# 2_MODUE.net
KiCad netlist of a schematic drawn in Altium Designer
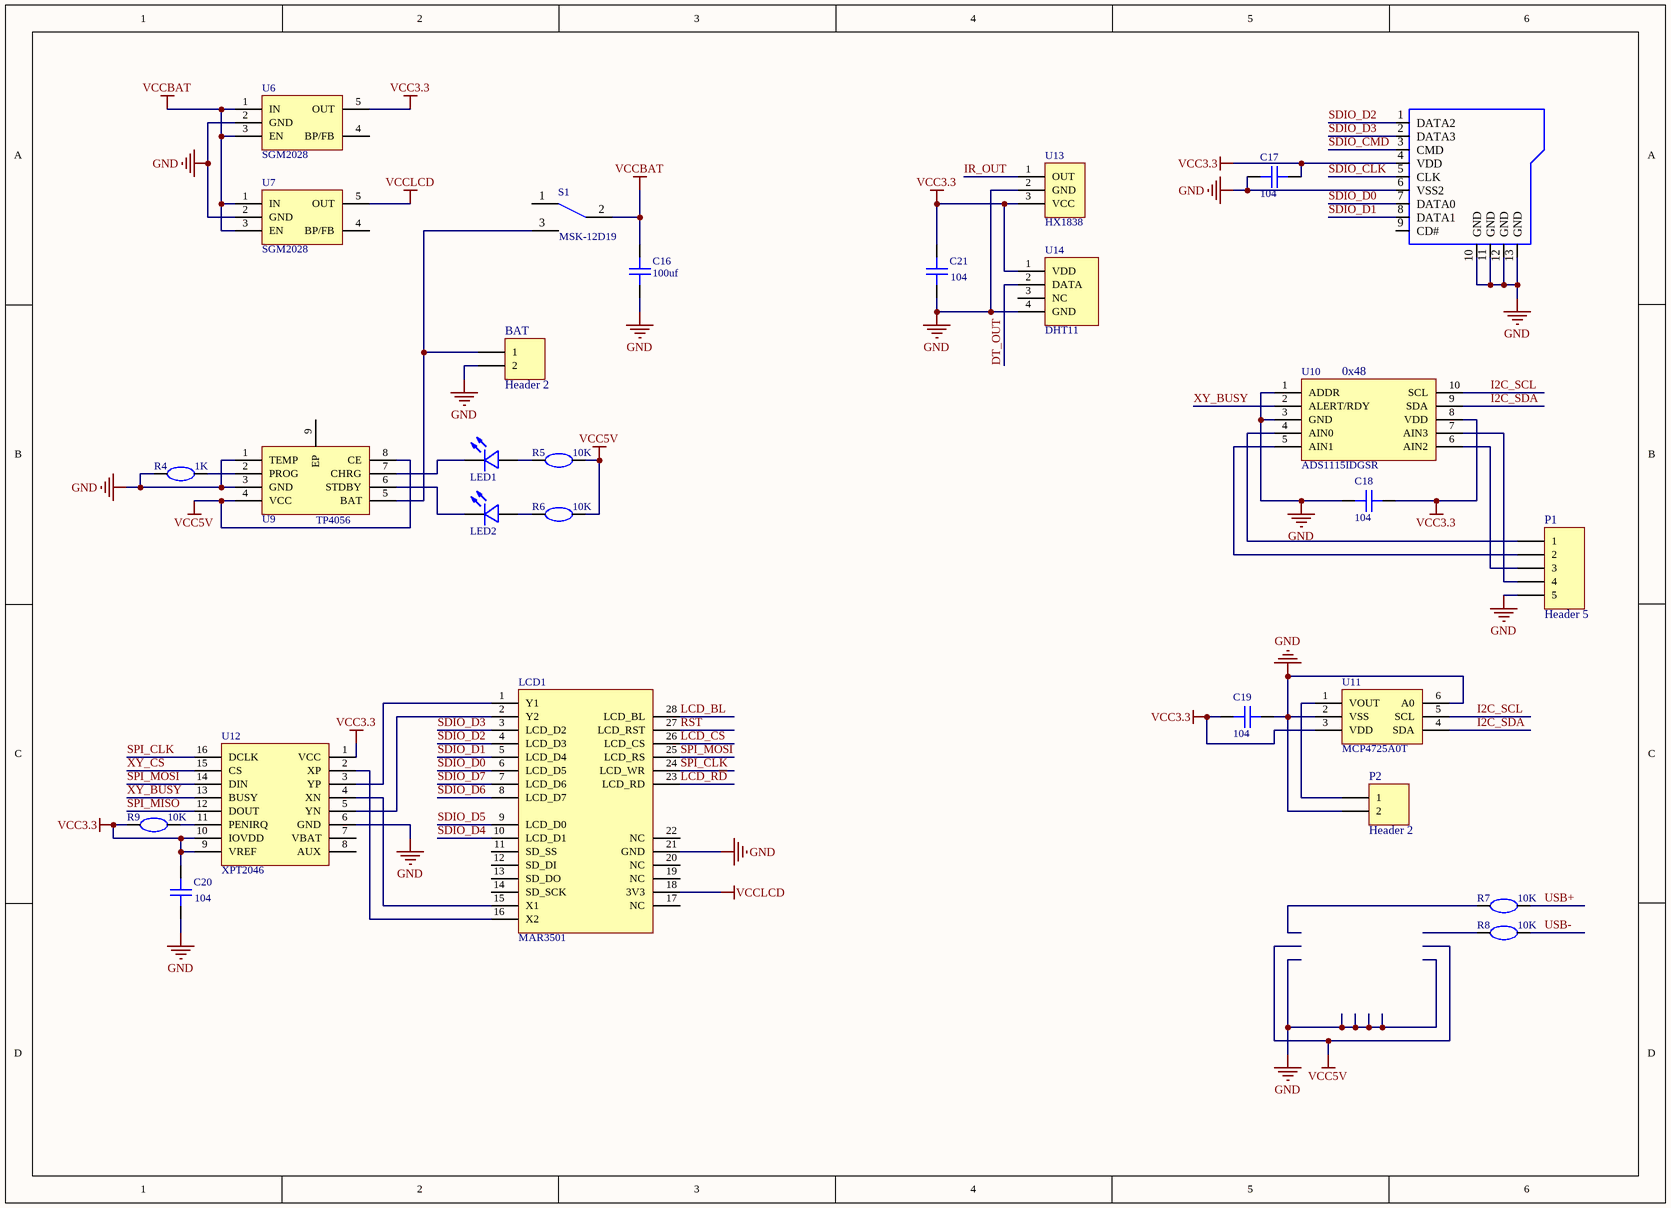
[diagram p0: 2_MODUE.schdoc]

(export (version "E")
  (design (tool "Eeschema 10.0.6"))
  (components
    (comp (ref "BAT")
      (value "Header 2")
      (footprint "HDR1X2")
      (description "Header, 2-Pin")
      (fields (field (name "PUBLISHER") "Altium Limited"))
      (libsource (lib "Miscellaneous Connectors") (part "Header 2"))
    )
    (comp (ref "C16") (value "100uf") (footprint "3528") (libsource (lib "sch") (part "CAP")))
    (comp (ref "C17") (value "104") (footprint "0402R") (libsource (lib "sch") (part "CAP")))
    (comp (ref "C18") (value "104") (footprint "0402R") (libsource (lib "sch") (part "CAP")))
    (comp (ref "C19") (value "104") (footprint "0402R") (libsource (lib "sch") (part "CAP")))
    (comp (ref "C20") (value "104") (footprint "0402R") (libsource (lib "sch") (part "CAP")))
    (comp (ref "C21") (value "104") (footprint "0402R") (libsource (lib "sch") (part "CAP")))
    (comp (ref "LCD1") (value "MAR3501") (footprint "MAR3501") (libsource (lib "sch") (part "MAR3501")))
    (comp (ref "LED1") (value "L-C292WDT-5A-YY") (footprint "0805") (libsource (lib "sch") (part "LED")))
    (comp (ref "LED2") (value "L-C292WDT-5A-YY") (footprint "0805") (libsource (lib "sch") (part "LED")))
    (comp (ref "P1")
      (value "Header 5")
      (footprint "HDR1X5")
      (description "Header, 5-Pin")
      (fields (field (name "PUBLISHER") "Altium Limited"))
      (libsource (lib "Miscellaneous Connectors") (part "Header 5"))
    )
    (comp (ref "P2")
      (value "Header 2")
      (footprint "HDR1X2")
      (description "Header, 2-Pin")
      (fields (field (name "PUBLISHER") "Altium Limited"))
      (libsource (lib "Miscellaneous Connectors") (part "Header 2"))
    )
    (comp (ref "R4") (value "1K") (footprint "0402R") (libsource (lib "sch") (part "RST")))
    (comp (ref "R5") (value "10K") (footprint "0402R") (libsource (lib "sch") (part "RST")))
    (comp (ref "R6") (value "10K") (footprint "0402R") (libsource (lib "sch") (part "RST")))
    (comp (ref "R7") (value "10K") (footprint "0805") (libsource (lib "sch") (part "RST")))
    (comp (ref "R8") (value "10K") (footprint "0805") (libsource (lib "sch") (part "RST")))
    (comp (ref "R9") (value "10K") (footprint "0402R") (libsource (lib "sch") (part "RST")))
    (comp (ref "S1")
      (value "MSK-12D19")
      (footprint "MSK-12D19")
      (fields (field (name "NAME") "MSK-12D19"))
      (libsource (lib "sch") (part "MSK-12D19"))
    )
    (comp (ref "TF1") (value "TF") (footprint "TF-SMD_XKTF-N02-N_1") (libsource (lib "sch") (part "TF")))
    (comp (ref "U6")
      (value "SGM2028")
      (footprint "SOT-23-5_L3.0-W1.7-P0.95-LS2.8-BR")
      (libsource (lib "sch") (part "SGM2028"))
    )
    (comp (ref "U7")
      (value "SGM2028")
      (footprint "SOT-23-5_L3.0-W1.7-P0.95-LS2.8-BR")
      (libsource (lib "sch") (part "SGM2028"))
    )
    (comp (ref "U9")
      (value "TP4056")
      (footprint "ESOP-8_L4.9-W3.9-P1.27-LS6.0-BL-EP")
      (libsource (lib "sch") (part "TP4056"))
    )
    (comp (ref "U10")
      (value "ADS1115IDGSR")
      (footprint "MSOP-10_L3.0-W3.0-P0.50-LS5.0-BL")
      (libsource (lib "sch") (part "ADS1115IDGSR"))
    )
    (comp (ref "U11")
      (value "MCP4725A0T")
      (footprint "SOT-23-6_L2.9-W1.6-P0.95-LS2.8-BR")
      (libsource (lib "sch") (part "MCP4725A0T"))
    )
    (comp (ref "U12")
      (value "XPT2046")
      (footprint "TSSOP-16_L5.0-W4.4-P0.65-LS6.4-BL")
      (libsource (lib "sch") (part "XPT2046"))
    )
    (comp (ref "U13") (value "HX1838") (footprint "HX1838") (libsource (lib "sch") (part "HX1838")))
    (comp (ref "U14") (value "DHT11") (footprint "SENSOR-TH_DHT11") (libsource (lib "sch") (part "DHT11")))
  )
  (nets
    (net (code "1") (name "/DT_OUT") (class "Default")
      (node (ref "U14") (pin "2") (pinfunction "DATA_2") (pintype "passive"))
    )
    (net (code "2") (name "/I2C_SCL") (class "Default")
      (node (ref "U10") (pin "10") (pinfunction "SCL_10") (pintype "passive"))
      (node (ref "U11") (pin "5") (pinfunction "SCL_5") (pintype "passive"))
    )
    (net (code "3") (name "/I2C_SDA") (class "Default")
      (node (ref "U10") (pin "9") (pinfunction "SDA_9") (pintype "passive"))
      (node (ref "U11") (pin "4") (pinfunction "SDA_4") (pintype "passive"))
    )
    (net (code "4") (name "/IR_OUT") (class "Default")
      (node (ref "U13") (pin "1") (pinfunction "OUT_1") (pintype "passive"))
    )
    (net (code "5") (name "/LCD_BL") (class "Default")
      (node (ref "LCD1") (pin "28") (pinfunction "LCD_BL_28") (pintype "passive"))
    )
    (net (code "6") (name "/LCD_CS") (class "Default")
      (node (ref "LCD1") (pin "26") (pinfunction "LCD_CS_26") (pintype "passive"))
    )
    (net (code "7") (name "/LCD_R~{D}") (class "Default")
      (node (ref "LCD1") (pin "23") (pinfunction "LCD_RD_23") (pintype "passive"))
    )
    (net (code "8") (name "/RST") (class "Default")
      (node (ref "LCD1") (pin "27") (pinfunction "LCD_RST_27") (pintype "passive"))
    )
    (net (code "9") (name "/SDIO_CLK") (class "Default")
      (node (ref "TF1") (pin "5") (pinfunction "CLK_5") (pintype "passive"))
    )
    (net (code "10") (name "/SDIO_CMD") (class "Default")
      (node (ref "TF1") (pin "3") (pinfunction "CMD_3") (pintype "passive"))
    )
    (net (code "11") (name "/SDIO_D0") (class "Default")
      (node (ref "LCD1") (pin "6") (pinfunction "LCD_D5_6") (pintype "passive"))
      (node (ref "TF1") (pin "7") (pinfunction "DATA0_7") (pintype "passive"))
    )
    (net (code "12") (name "/SDIO_D1") (class "Default")
      (node (ref "LCD1") (pin "5") (pinfunction "LCD_D4_5") (pintype "passive"))
      (node (ref "TF1") (pin "8") (pinfunction "DATA1_8") (pintype "passive"))
    )
    (net (code "13") (name "/SDIO_D2") (class "Default")
      (node (ref "LCD1") (pin "4") (pinfunction "LCD_D3_4") (pintype "passive"))
      (node (ref "TF1") (pin "1") (pinfunction "DATA2_1") (pintype "passive"))
    )
    (net (code "14") (name "/SDIO_D3") (class "Default")
      (node (ref "LCD1") (pin "3") (pinfunction "LCD_D2_3") (pintype "passive"))
      (node (ref "TF1") (pin "2") (pinfunction "DATA3_2") (pintype "passive"))
    )
    (net (code "15") (name "/SDIO_D4") (class "Default")
      (node (ref "LCD1") (pin "10") (pinfunction "LCD_D1_10") (pintype "passive"))
    )
    (net (code "16") (name "/SDIO_D5") (class "Default")
      (node (ref "LCD1") (pin "9") (pinfunction "LCD_D0_9") (pintype "passive"))
    )
    (net (code "17") (name "/SDIO_D6") (class "Default")
      (node (ref "LCD1") (pin "8") (pinfunction "LCD_D7_8") (pintype "passive"))
    )
    (net (code "18") (name "/SDIO_D7") (class "Default")
      (node (ref "LCD1") (pin "7") (pinfunction "LCD_D6_7") (pintype "passive"))
    )
    (net (code "19") (name "/SPI_CLK") (class "Default")
      (node (ref "LCD1") (pin "24") (pinfunction "LCD_WR_24") (pintype "passive"))
      (node (ref "U12") (pin "16") (pinfunction "DCLK_16") (pintype "passive"))
    )
    (net (code "20") (name "/SPI_MISO") (class "Default")
      (node (ref "U12") (pin "12") (pinfunction "DOUT_12") (pintype "passive"))
    )
    (net (code "21") (name "/SPI_MOSI") (class "Default")
      (node (ref "LCD1") (pin "25") (pinfunction "LCD_RS_25") (pintype "passive"))
      (node (ref "U12") (pin "14") (pinfunction "DIN_14") (pintype "passive"))
    )
    (net (code "22") (name "/USB+") (class "Default")
      (node (ref "R7") (pin "2") (pinfunction "2_2") (pintype "passive"))
    )
    (net (code "23") (name "/USB-") (class "Default")
      (node (ref "R8") (pin "2") (pinfunction "2_2") (pintype "passive"))
    )
    (net (code "24") (name "/XY_BUSY") (class "Default")
      (node (ref "U10") (pin "2") (pinfunction "ALERT/RDY_2") (pintype "passive"))
      (node (ref "U12") (pin "13") (pinfunction "BUSY_13") (pintype "passive"))
    )
    (net (code "25") (name "/XY_CS") (class "Default")
      (node (ref "U12") (pin "15") (pinfunction "CS_15") (pintype "passive"))
    )
    (net (code "26") (name "GND") (class "Default")
      (node (ref "BAT") (pin "2") (pinfunction "2_2") (pintype "passive"))
      (node (ref "C16") (pin "1") (pinfunction "1_1") (pintype "passive"))
      (node (ref "C17") (pin "2") (pinfunction "2_2") (pintype "passive"))
      (node (ref "C18") (pin "2") (pinfunction "2_2") (pintype "passive"))
      (node (ref "C19") (pin "2") (pinfunction "2_2") (pintype "passive"))
      (node (ref "C20") (pin "1") (pinfunction "1_1") (pintype "passive"))
      (node (ref "C21") (pin "1") (pinfunction "1_1") (pintype "passive"))
      (node (ref "LCD1") (pin "21") (pinfunction "GND_21") (pintype "passive"))
      (node (ref "P1") (pin "5") (pinfunction "5_5") (pintype "passive"))
      (node (ref "P2") (pin "2") (pinfunction "2_2") (pintype "passive"))
      (node (ref "R4") (pin "1") (pinfunction "1_1") (pintype "passive"))
      (node (ref "TF1") (pin "10") (pinfunction "GND_10") (pintype "passive"))
      (node (ref "TF1") (pin "11") (pinfunction "GND_11") (pintype "passive"))
      (node (ref "TF1") (pin "12") (pinfunction "GND_12") (pintype "passive"))
      (node (ref "TF1") (pin "13") (pinfunction "GND_13") (pintype "passive"))
      (node (ref "TF1") (pin "6") (pinfunction "VSS2_6") (pintype "passive"))
      (node (ref "U10") (pin "1") (pinfunction "ADDR_1") (pintype "passive"))
      (node (ref "U10") (pin "3") (pinfunction "GND_3") (pintype "passive"))
      (node (ref "U11") (pin "2") (pinfunction "VSS_2") (pintype "passive"))
      (node (ref "U11") (pin "6") (pinfunction "A0_6") (pintype "passive"))
      (node (ref "U12") (pin "6") (pinfunction "GND_6") (pintype "passive"))
      (node (ref "U13") (pin "2") (pinfunction "GND_2") (pintype "passive"))
      (node (ref "U14") (pin "4") (pinfunction "GND_4") (pintype "passive"))
      (node (ref "U6") (pin "2") (pinfunction "GND_2") (pintype "passive"))
      (node (ref "U7") (pin "2") (pinfunction "GND_2") (pintype "passive"))
      (node (ref "U9") (pin "1") (pinfunction "TEMP_1") (pintype "passive"))
      (node (ref "U9") (pin "3") (pinfunction "GND_3") (pintype "passive"))
    )
    (net (code "27") (name "Net-(LCD1-X1)") (class "Default")
      (node (ref "LCD1") (pin "15") (pinfunction "X1_15") (pintype "passive"))
      (node (ref "U12") (pin "4") (pinfunction "XN_4") (pintype "passive"))
    )
    (net (code "28") (name "Net-(LCD1-X2)") (class "Default")
      (node (ref "LCD1") (pin "16") (pinfunction "X2_16") (pintype "passive"))
      (node (ref "U12") (pin "2") (pinfunction "XP_2") (pintype "passive"))
    )
    (net (code "29") (name "Net-(LCD1-Y1)") (class "Default")
      (node (ref "LCD1") (pin "1") (pinfunction "Y1_1") (pintype "passive"))
      (node (ref "U12") (pin "3") (pinfunction "YP_3") (pintype "passive"))
    )
    (net (code "30") (name "Net-(LCD1-Y2)") (class "Default")
      (node (ref "LCD1") (pin "2") (pinfunction "Y2_2") (pintype "passive"))
      (node (ref "U12") (pin "5") (pinfunction "YN_5") (pintype "passive"))
    )
    (net (code "31") (name "Net-(LED1-+)") (class "Default")
      (node (ref "LED1") (pin "1") (pinfunction "+_1") (pintype "passive"))
      (node (ref "R5") (pin "1") (pinfunction "1_1") (pintype "passive"))
    )
    (net (code "32") (name "Net-(LED1--)") (class "Default")
      (node (ref "LED1") (pin "2") (pinfunction "-_2") (pintype "passive"))
      (node (ref "U9") (pin "7") (pinfunction "CHRG_7") (pintype "passive"))
    )
    (net (code "33") (name "Net-(LED2-+)") (class "Default")
      (node (ref "LED2") (pin "1") (pinfunction "+_1") (pintype "passive"))
      (node (ref "R6") (pin "1") (pinfunction "1_1") (pintype "passive"))
    )
    (net (code "34") (name "Net-(LED2--)") (class "Default")
      (node (ref "LED2") (pin "2") (pinfunction "-_2") (pintype "passive"))
      (node (ref "U9") (pin "6") (pinfunction "STDBY_6") (pintype "passive"))
    )
    (net (code "35") (name "Net-(S1-C)") (class "Default")
      (node (ref "BAT") (pin "1") (pinfunction "1_1") (pintype "passive"))
      (node (ref "S1") (pin "3") (pinfunction "C_3") (pintype "passive"))
      (node (ref "U9") (pin "5") (pinfunction "BAT_5") (pintype "passive"))
    )
    (net (code "36") (name "Net-(U9-PROG)") (class "Default")
      (node (ref "R4") (pin "2") (pinfunction "2_2") (pintype "passive"))
      (node (ref "U9") (pin "2") (pinfunction "PROG_2") (pintype "passive"))
    )
    (net (code "37") (name "Net-(U10-AIN0)") (class "Default")
      (node (ref "P1") (pin "1") (pinfunction "1_1") (pintype "passive"))
      (node (ref "U10") (pin "4") (pinfunction "AIN0_4") (pintype "passive"))
    )
    (net (code "38") (name "Net-(U10-AIN1)") (class "Default")
      (node (ref "P1") (pin "2") (pinfunction "2_2") (pintype "passive"))
      (node (ref "U10") (pin "5") (pinfunction "AIN1_5") (pintype "passive"))
    )
    (net (code "39") (name "Net-(U10-AIN2)") (class "Default")
      (node (ref "P1") (pin "3") (pinfunction "3_3") (pintype "passive"))
      (node (ref "U10") (pin "6") (pinfunction "AIN2_6") (pintype "passive"))
    )
    (net (code "40") (name "Net-(U10-AIN3)") (class "Default")
      (node (ref "P1") (pin "4") (pinfunction "4_4") (pintype "passive"))
      (node (ref "U10") (pin "7") (pinfunction "AIN3_7") (pintype "passive"))
    )
    (net (code "41") (name "Net-(U11-VOUT)") (class "Default")
      (node (ref "P2") (pin "1") (pinfunction "1_1") (pintype "passive"))
      (node (ref "U11") (pin "1") (pinfunction "VOUT_1") (pintype "passive"))
    )
    (net (code "42") (name "Net-(U12-PENIRQ)") (class "Default")
      (node (ref "R9") (pin "2") (pinfunction "2_2") (pintype "passive"))
      (node (ref "U12") (pin "11") (pinfunction "PENIRQ_11") (pintype "passive"))
    )
    (net (code "43") (name "VCC3.3") (class "Default")
      (node (ref "C17") (pin "1") (pinfunction "1_1") (pintype "passive"))
      (node (ref "C18") (pin "1") (pinfunction "1_1") (pintype "passive"))
      (node (ref "C19") (pin "1") (pinfunction "1_1") (pintype "passive"))
      (node (ref "C20") (pin "2") (pinfunction "2_2") (pintype "passive"))
      (node (ref "C21") (pin "2") (pinfunction "2_2") (pintype "passive"))
      (node (ref "R9") (pin "1") (pinfunction "1_1") (pintype "passive"))
      (node (ref "TF1") (pin "4") (pinfunction "VDD_4") (pintype "passive"))
      (node (ref "U10") (pin "8") (pinfunction "VDD_8") (pintype "passive"))
      (node (ref "U11") (pin "3") (pinfunction "VDD_3") (pintype "passive"))
      (node (ref "U12") (pin "1") (pinfunction "VCC_1") (pintype "passive"))
      (node (ref "U12") (pin "10") (pinfunction "IOVDD_10") (pintype "passive"))
      (node (ref "U12") (pin "9") (pinfunction "VREF_9") (pintype "passive"))
      (node (ref "U13") (pin "3") (pinfunction "VCC_3") (pintype "passive"))
      (node (ref "U14") (pin "1") (pinfunction "VDD_1") (pintype "passive"))
      (node (ref "U6") (pin "5") (pinfunction "OUT_5") (pintype "passive"))
    )
    (net (code "44") (name "VCC5V") (class "Default")
      (node (ref "R5") (pin "2") (pinfunction "2_2") (pintype "passive"))
      (node (ref "R6") (pin "2") (pinfunction "2_2") (pintype "passive"))
      (node (ref "U9") (pin "4") (pinfunction "VCC_4") (pintype "passive"))
      (node (ref "U9") (pin "8") (pinfunction "CE_8") (pintype "passive"))
    )
    (net (code "45") (name "VCCBAT") (class "Default")
      (node (ref "C16") (pin "2") (pinfunction "2_2") (pintype "passive"))
      (node (ref "S1") (pin "2") (pinfunction "B_2") (pintype "passive"))
      (node (ref "U6") (pin "1") (pinfunction "IN_1") (pintype "passive"))
      (node (ref "U6") (pin "3") (pinfunction "EN_3") (pintype "passive"))
      (node (ref "U7") (pin "1") (pinfunction "IN_1") (pintype "passive"))
      (node (ref "U7") (pin "3") (pinfunction "EN_3") (pintype "passive"))
    )
    (net (code "46") (name "VCCLCD") (class "Default")
      (node (ref "LCD1") (pin "18") (pinfunction "3V3_18") (pintype "passive"))
      (node (ref "U7") (pin "5") (pinfunction "OUT_5") (pintype "passive"))
    )
    (net (code "47") (name "unconnected-(LCD1-NC-Pad17)") (class "Default")
      (node (ref "LCD1") (pin "17") (pinfunction "NC_17") (pintype "passive"))
    )
    (net (code "48") (name "unconnected-(LCD1-NC-Pad19)") (class "Default")
      (node (ref "LCD1") (pin "19") (pinfunction "NC_19") (pintype "passive"))
    )
    (net (code "49") (name "unconnected-(LCD1-NC-Pad20)") (class "Default")
      (node (ref "LCD1") (pin "20") (pinfunction "NC_20") (pintype "passive"))
    )
    (net (code "50") (name "unconnected-(LCD1-NC-Pad22)") (class "Default")
      (node (ref "LCD1") (pin "22") (pinfunction "NC_22") (pintype "passive"))
    )
    (net (code "51") (name "unconnected-(LCD1-SD_DI-Pad12)") (class "Default")
      (node (ref "LCD1") (pin "12") (pinfunction "SD_DI_12") (pintype "passive"))
    )
    (net (code "52") (name "unconnected-(LCD1-SD_DO-Pad13)") (class "Default")
      (node (ref "LCD1") (pin "13") (pinfunction "SD_DO_13") (pintype "passive"))
    )
    (net (code "53") (name "unconnected-(LCD1-SD_SCK-Pad14)") (class "Default")
      (node (ref "LCD1") (pin "14") (pinfunction "SD_SCK_14") (pintype "passive"))
    )
    (net (code "54") (name "unconnected-(LCD1-SD_SS-Pad11)") (class "Default")
      (node (ref "LCD1") (pin "11") (pinfunction "SD_SS_11") (pintype "passive"))
    )
    (net (code "55") (name "unconnected-(R7-Pad1)") (class "Default")
      (node (ref "R7") (pin "1") (pinfunction "1_1") (pintype "passive"))
    )
    (net (code "56") (name "unconnected-(R8-Pad1)") (class "Default")
      (node (ref "R8") (pin "1") (pinfunction "1_1") (pintype "passive"))
    )
    (net (code "57") (name "unconnected-(S1-A-Pad1)") (class "Default")
      (node (ref "S1") (pin "1") (pinfunction "A_1") (pintype "passive"))
    )
    (net (code "58") (name "unconnected-(TF1-CD#-Pad9)") (class "Default")
      (node (ref "TF1") (pin "9") (pinfunction "CD#_9") (pintype "passive"))
    )
    (net (code "59") (name "unconnected-(U6-BP{slash}FB-Pad4)") (class "Default")
      (node (ref "U6") (pin "4") (pinfunction "BP/FB_4") (pintype "passive"))
    )
    (net (code "60") (name "unconnected-(U7-BP{slash}FB-Pad4)") (class "Default")
      (node (ref "U7") (pin "4") (pinfunction "BP/FB_4") (pintype "passive"))
    )
    (net (code "61") (name "unconnected-(U9-EP-Pad9)") (class "Default")
      (node (ref "U9") (pin "9") (pinfunction "EP_9") (pintype "passive"))
    )
    (net (code "62") (name "unconnected-(U12-AUX-Pad8)") (class "Default")
      (node (ref "U12") (pin "8") (pinfunction "AUX_8") (pintype "passive"))
    )
    (net (code "63") (name "unconnected-(U12-VBAT-Pad7)") (class "Default")
      (node (ref "U12") (pin "7") (pinfunction "VBAT_7") (pintype "passive"))
    )
    (net (code "64") (name "unconnected-(U14-NC-Pad3)") (class "Default")
      (node (ref "U14") (pin "3") (pinfunction "NC_3") (pintype "passive"))
    )
  )
)
